# ZYNQ400-DDR.net
KiCad netlist of a schematic drawn in Altium Designer
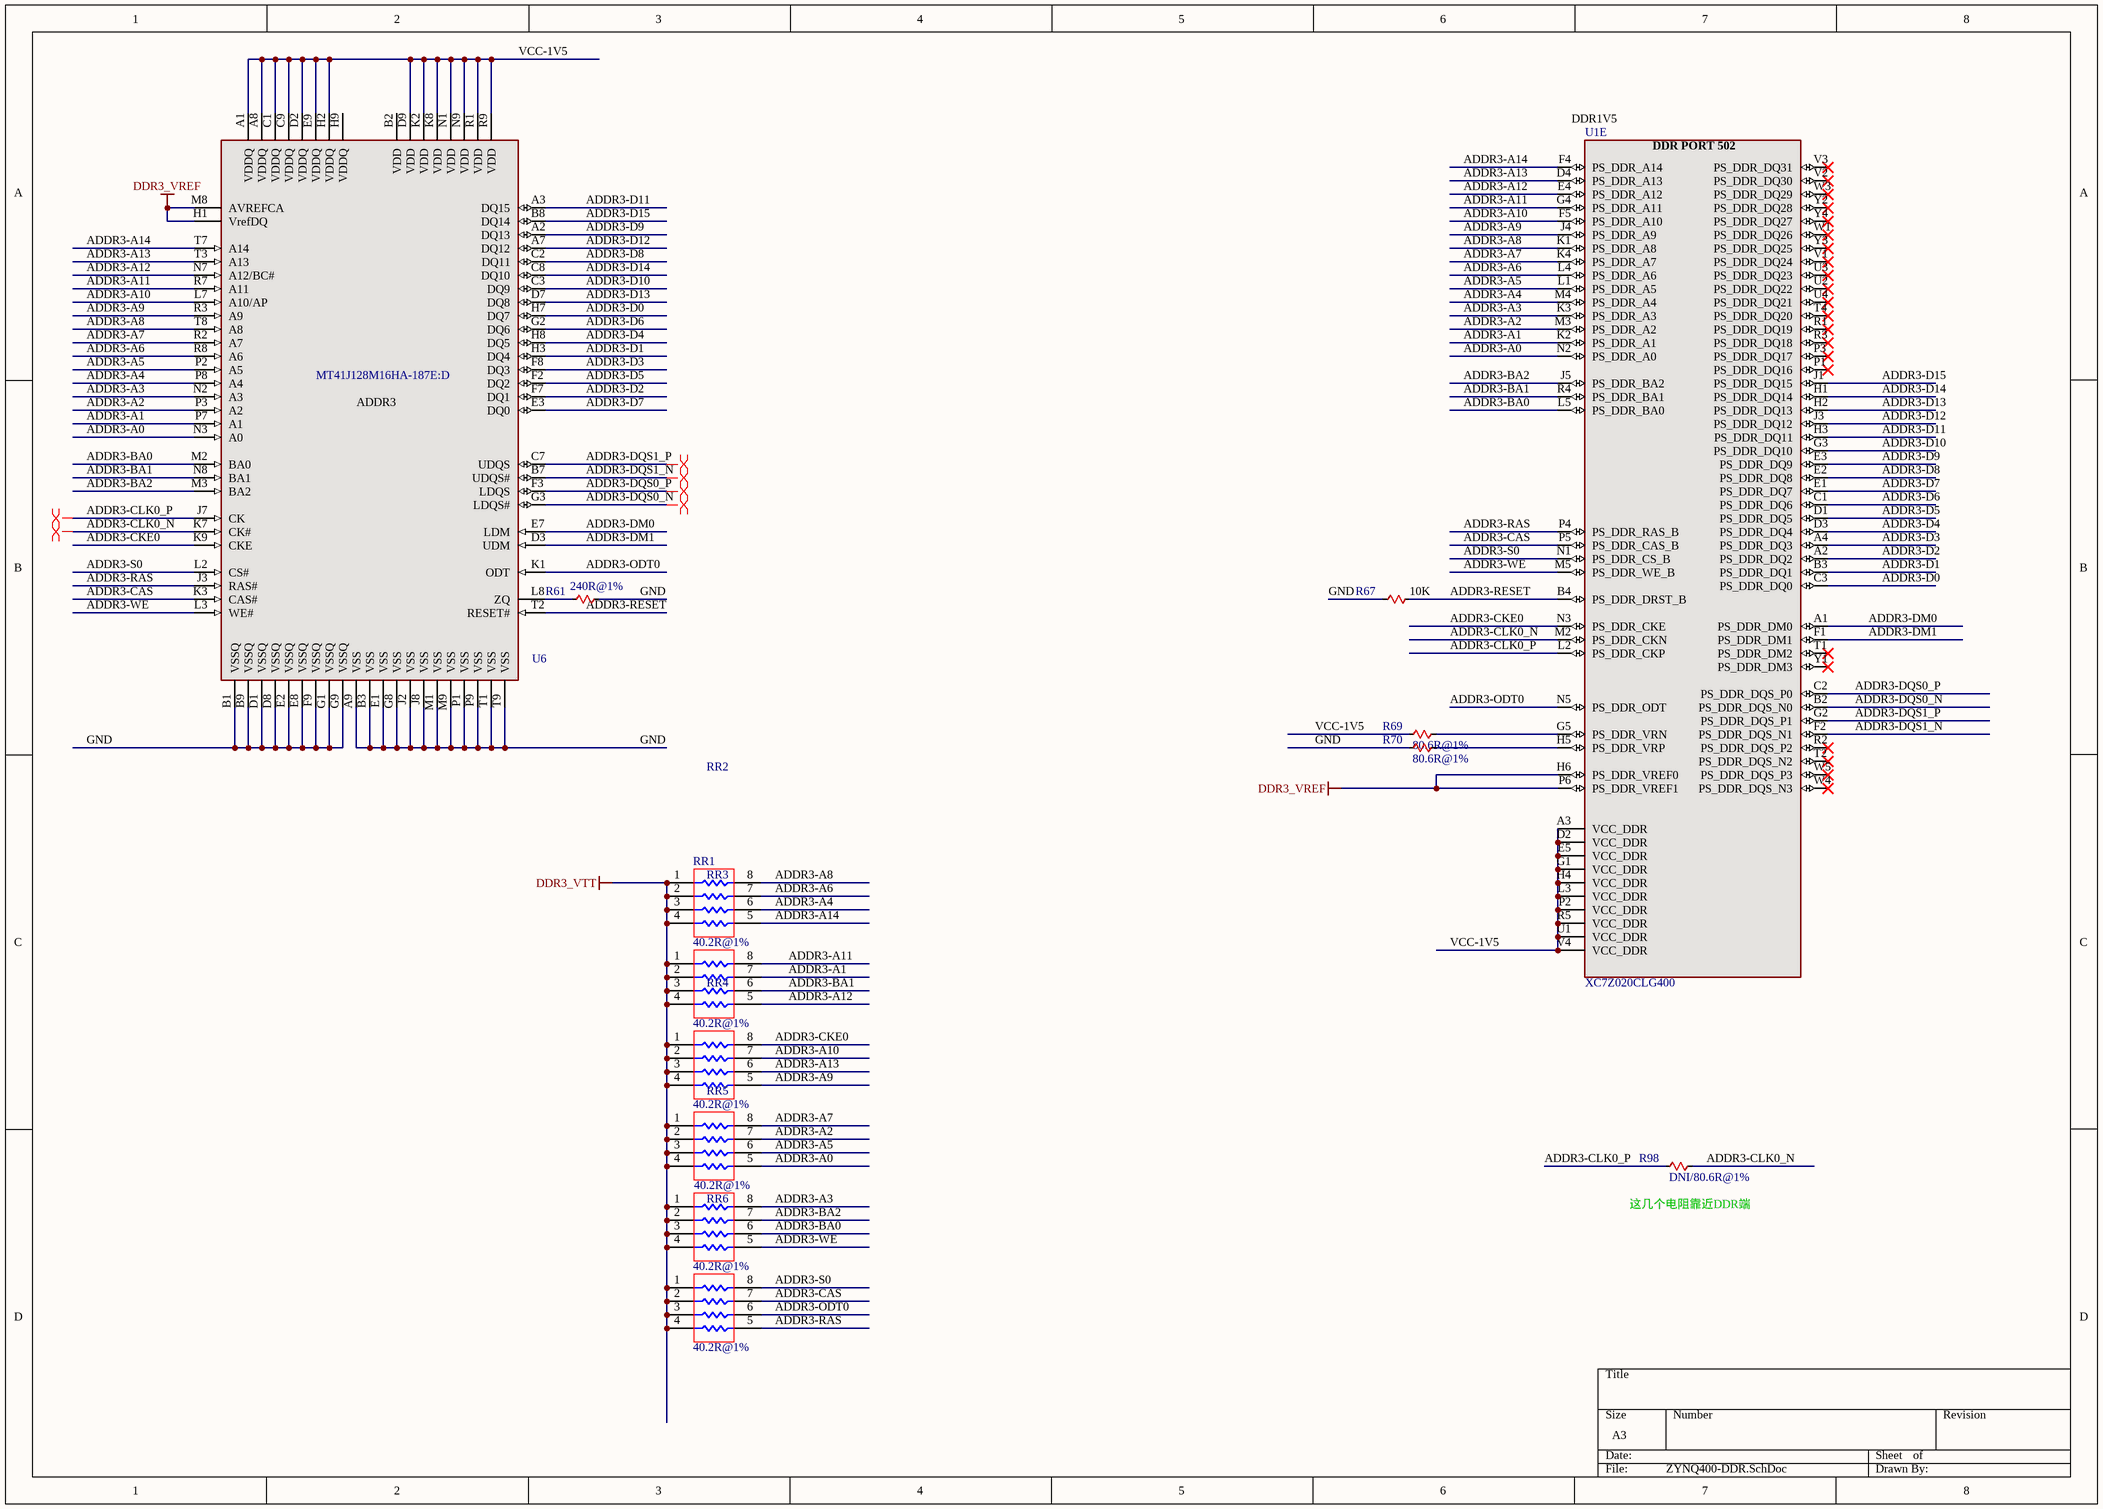
[diagram p0: ZYNQ400-DDR.SchDoc]

(export (version "E")
  (design (tool "Eeschema 10.0.6"))
  (components
    (comp (ref "R61")
      (value "240R@1%")
      (footprint "0402")
      (description "Generic Resistor")
      (libsource (lib "Digilent") (part "RESISTOR"))
    )
    (comp (ref "R67")
      (value "10K")
      (footprint "0402")
      (description "Generic Resistor")
      (libsource (lib "Digilent") (part "RESISTOR"))
    )
    (comp (ref "R69")
      (value "80.6R@1%")
      (footprint "0402")
      (description "Generic Resistor")
      (libsource (lib "Digilent") (part "RESISTOR"))
    )
    (comp (ref "R70")
      (value "80.6R@1%")
      (footprint "0402")
      (description "Generic Resistor")
      (libsource (lib "Digilent") (part "RESISTOR"))
    )
    (comp (ref "R98")
      (value "DNI/80.6R@1%")
      (footprint "0402")
      (description "Generic Resistor")
      (libsource (lib "Digilent") (part "RESISTOR"))
    )
    (comp (ref "RR1")
      (value "40.2R@1%")
      (footprint "R0402*4")
      (description "Isolated Resistor Network")
      (fields (field (name "PUBLISHER") "Altium Limited"))
      (libsource (lib "ipc400") (part "Res -4"))
    )
    (comp (ref "RR2")
      (value "40.2R@1%")
      (footprint "R0402*4")
      (description "Isolated Resistor Network")
      (fields (field (name "PUBLISHER") "Altium Limited"))
      (libsource (lib "ipc400") (part "Res -4"))
    )
    (comp (ref "RR3")
      (value "40.2R@1%")
      (footprint "R0402*4")
      (description "Isolated Resistor Network")
      (fields (field (name "PUBLISHER") "Altium Limited"))
      (libsource (lib "ipc400") (part "Res -4"))
    )
    (comp (ref "RR4")
      (value "40.2R@1%")
      (footprint "R0402*4")
      (description "Isolated Resistor Network")
      (fields (field (name "PUBLISHER") "Altium Limited"))
      (libsource (lib "ipc400") (part "Res -4"))
    )
    (comp (ref "RR5")
      (value "40.2R@1%")
      (footprint "R0402*4")
      (description "Isolated Resistor Network")
      (fields (field (name "PUBLISHER") "Altium Limited"))
      (libsource (lib "ipc400") (part "Res -4"))
    )
    (comp (ref "RR6")
      (value "40.2R@1%")
      (footprint "R0402*4")
      (description "Isolated Resistor Network")
      (fields (field (name "PUBLISHER") "Altium Limited"))
      (libsource (lib "ipc400") (part "Res -4"))
    )
    (comp (ref "U1")
      (value "XC7Z020CLG400")
      (footprint "CLG400")
      (description "Zynq 7000 FPGA 20 Die, in a CSG 484 Package")
      (fields (field (name "MANUFACTURER") "Xilinx"))
      (libsource (lib "gjws") (part "XC7Z020-CLG400"))
    )
    (comp (ref "U6")
      (value "MT41J128M16HA-187E:D")
      (footprint "FBGA96")
      (description "DDR3 SDRAM 2Gb x4, x8, x16")
      (fields (field (name "MANUFACTURER") "Micron"))
      (libsource (lib "Digilent") (part "MT41JxxxMxx"))
    )
  )
  (nets
    (net (code "1") (name "/ADDR3-A0") (class "Default")
      (node (ref "RR4") (pin "5") (pinfunction "5_5") (pintype "passive"))
      (node (ref "U1") (pin "N2") (pinfunction "PS_DDR_A0_N2") (pintype "bidirectional"))
      (node (ref "U6") (pin "N3") (pinfunction "A0_N3") (pintype "input"))
    )
    (net (code "2") (name "/ADDR3-A1") (class "Default")
      (node (ref "RR2") (pin "7") (pinfunction "7_7") (pintype "passive"))
      (node (ref "U1") (pin "K2") (pinfunction "PS_DDR_A1_K2") (pintype "bidirectional"))
      (node (ref "U6") (pin "P7") (pinfunction "A1_P7") (pintype "input"))
    )
    (net (code "3") (name "/ADDR3-A2") (class "Default")
      (node (ref "RR4") (pin "7") (pinfunction "7_7") (pintype "passive"))
      (node (ref "U1") (pin "M3") (pinfunction "PS_DDR_A2_M3") (pintype "bidirectional"))
      (node (ref "U6") (pin "P3") (pinfunction "A2_P3") (pintype "input"))
    )
    (net (code "4") (name "/ADDR3-A3") (class "Default")
      (node (ref "RR5") (pin "8") (pinfunction "8_8") (pintype "passive"))
      (node (ref "U1") (pin "K3") (pinfunction "PS_DDR_A3_K3") (pintype "bidirectional"))
      (node (ref "U6") (pin "N2") (pinfunction "A3_N2") (pintype "input"))
    )
    (net (code "5") (name "/ADDR3-A4") (class "Default")
      (node (ref "RR1") (pin "6") (pinfunction "6_6") (pintype "passive"))
      (node (ref "U1") (pin "M4") (pinfunction "PS_DDR_A4_M4") (pintype "bidirectional"))
      (node (ref "U6") (pin "P8") (pinfunction "A4_P8") (pintype "input"))
    )
    (net (code "6") (name "/ADDR3-A5") (class "Default")
      (node (ref "RR4") (pin "6") (pinfunction "6_6") (pintype "passive"))
      (node (ref "U1") (pin "L1") (pinfunction "PS_DDR_A5_L1") (pintype "bidirectional"))
      (node (ref "U6") (pin "P2") (pinfunction "A5_P2") (pintype "input"))
    )
    (net (code "7") (name "/ADDR3-A6") (class "Default")
      (node (ref "RR1") (pin "7") (pinfunction "7_7") (pintype "passive"))
      (node (ref "U1") (pin "L4") (pinfunction "PS_DDR_A6_L4") (pintype "bidirectional"))
      (node (ref "U6") (pin "R8") (pinfunction "A6_R8") (pintype "input"))
    )
    (net (code "8") (name "/ADDR3-A7") (class "Default")
      (node (ref "RR4") (pin "8") (pinfunction "8_8") (pintype "passive"))
      (node (ref "U1") (pin "K4") (pinfunction "PS_DDR_A7_K4") (pintype "bidirectional"))
      (node (ref "U6") (pin "R2") (pinfunction "A7_R2") (pintype "input"))
    )
    (net (code "9") (name "/ADDR3-A8") (class "Default")
      (node (ref "RR1") (pin "8") (pinfunction "8_8") (pintype "passive"))
      (node (ref "U1") (pin "K1") (pinfunction "PS_DDR_A8_K1") (pintype "bidirectional"))
      (node (ref "U6") (pin "T8") (pinfunction "A8_T8") (pintype "input"))
    )
    (net (code "10") (name "/ADDR3-A9") (class "Default")
      (node (ref "RR3") (pin "5") (pinfunction "5_5") (pintype "passive"))
      (node (ref "U1") (pin "J4") (pinfunction "PS_DDR_A9_J4") (pintype "bidirectional"))
      (node (ref "U6") (pin "R3") (pinfunction "A9_R3") (pintype "input"))
    )
    (net (code "11") (name "/ADDR3-A10") (class "Default")
      (node (ref "RR3") (pin "7") (pinfunction "7_7") (pintype "passive"))
      (node (ref "U1") (pin "F5") (pinfunction "PS_DDR_A10_F5") (pintype "bidirectional"))
      (node (ref "U6") (pin "L7") (pinfunction "A10/AP_L7") (pintype "input"))
    )
    (net (code "12") (name "/ADDR3-A11") (class "Default")
      (node (ref "RR2") (pin "8") (pinfunction "8_8") (pintype "passive"))
      (node (ref "U1") (pin "G4") (pinfunction "PS_DDR_A11_G4") (pintype "bidirectional"))
      (node (ref "U6") (pin "R7") (pinfunction "A11_R7") (pintype "input"))
    )
    (net (code "13") (name "/ADDR3-A12") (class "Default")
      (node (ref "RR2") (pin "5") (pinfunction "5_5") (pintype "passive"))
      (node (ref "U1") (pin "E4") (pinfunction "PS_DDR_A12_E4") (pintype "bidirectional"))
      (node (ref "U6") (pin "N7") (pinfunction "A12/BC#_N7") (pintype "input"))
    )
    (net (code "14") (name "/ADDR3-A13") (class "Default")
      (node (ref "RR3") (pin "6") (pinfunction "6_6") (pintype "passive"))
      (node (ref "U1") (pin "D4") (pinfunction "PS_DDR_A13_D4") (pintype "bidirectional"))
      (node (ref "U6") (pin "T3") (pinfunction "A13_T3") (pintype "input"))
    )
    (net (code "15") (name "/ADDR3-A14") (class "Default")
      (node (ref "RR1") (pin "5") (pinfunction "5_5") (pintype "passive"))
      (node (ref "U1") (pin "F4") (pinfunction "PS_DDR_A14_F4") (pintype "bidirectional"))
      (node (ref "U6") (pin "T7") (pinfunction "A14_T7") (pintype "input"))
    )
    (net (code "16") (name "/ADDR3-BA0") (class "Default")
      (node (ref "RR5") (pin "6") (pinfunction "6_6") (pintype "passive"))
      (node (ref "U1") (pin "L5") (pinfunction "PS_DDR_BA0_L5") (pintype "bidirectional"))
      (node (ref "U6") (pin "M2") (pinfunction "BA0_M2") (pintype "input"))
    )
    (net (code "17") (name "/ADDR3-BA1") (class "Default")
      (node (ref "RR2") (pin "6") (pinfunction "6_6") (pintype "passive"))
      (node (ref "U1") (pin "R4") (pinfunction "PS_DDR_BA1_R4") (pintype "bidirectional"))
      (node (ref "U6") (pin "N8") (pinfunction "BA1_N8") (pintype "input"))
    )
    (net (code "18") (name "/ADDR3-BA2") (class "Default")
      (node (ref "RR5") (pin "7") (pinfunction "7_7") (pintype "passive"))
      (node (ref "U1") (pin "J5") (pinfunction "PS_DDR_BA2_J5") (pintype "bidirectional"))
      (node (ref "U6") (pin "M3") (pinfunction "BA2_M3") (pintype "input"))
    )
    (net (code "19") (name "/ADDR3-CAS") (class "Default")
      (node (ref "RR6") (pin "7") (pinfunction "7_7") (pintype "passive"))
      (node (ref "U1") (pin "P5") (pinfunction "PS_DDR_CAS_B_P5") (pintype "bidirectional"))
      (node (ref "U6") (pin "K3") (pinfunction "CAS#_K3") (pintype "input"))
    )
    (net (code "20") (name "/ADDR3-CKE0") (class "Default")
      (node (ref "RR3") (pin "8") (pinfunction "8_8") (pintype "passive"))
      (node (ref "U1") (pin "N3") (pinfunction "PS_DDR_CKE_N3") (pintype "bidirectional"))
      (node (ref "U6") (pin "K9") (pinfunction "CKE_K9") (pintype "input"))
    )
    (net (code "21") (name "/ADDR3-CLK0_N") (class "Default")
      (node (ref "R98") (pin "2") (pinfunction "2_2") (pintype "passive"))
      (node (ref "U1") (pin "M2") (pinfunction "PS_DDR_CKN_M2") (pintype "bidirectional"))
      (node (ref "U6") (pin "K7") (pinfunction "CK#_K7") (pintype "input"))
    )
    (net (code "22") (name "/ADDR3-CLK0_P") (class "Default")
      (node (ref "R98") (pin "1") (pinfunction "1_1") (pintype "passive"))
      (node (ref "U1") (pin "L2") (pinfunction "PS_DDR_CKP_L2") (pintype "bidirectional"))
      (node (ref "U6") (pin "J7") (pinfunction "CK_J7") (pintype "input"))
    )
    (net (code "23") (name "/ADDR3-D0") (class "Default")
      (node (ref "U1") (pin "C3") (pinfunction "PS_DDR_DQ0_C3") (pintype "bidirectional"))
      (node (ref "U6") (pin "H7") (pinfunction "DQ7_H7") (pintype "bidirectional"))
    )
    (net (code "24") (name "/ADDR3-D1") (class "Default")
      (node (ref "U1") (pin "B3") (pinfunction "PS_DDR_DQ1_B3") (pintype "bidirectional"))
      (node (ref "U6") (pin "H3") (pinfunction "DQ4_H3") (pintype "bidirectional"))
    )
    (net (code "25") (name "/ADDR3-D2") (class "Default")
      (node (ref "U1") (pin "A2") (pinfunction "PS_DDR_DQ2_A2") (pintype "bidirectional"))
      (node (ref "U6") (pin "F7") (pinfunction "DQ1_F7") (pintype "bidirectional"))
    )
    (net (code "26") (name "/ADDR3-D3") (class "Default")
      (node (ref "U1") (pin "A4") (pinfunction "PS_DDR_DQ3_A4") (pintype "bidirectional"))
      (node (ref "U6") (pin "F8") (pinfunction "DQ3_F8") (pintype "bidirectional"))
    )
    (net (code "27") (name "/ADDR3-D4") (class "Default")
      (node (ref "U1") (pin "D3") (pinfunction "PS_DDR_DQ4_D3") (pintype "bidirectional"))
      (node (ref "U6") (pin "H8") (pinfunction "DQ5_H8") (pintype "bidirectional"))
    )
    (net (code "28") (name "/ADDR3-D5") (class "Default")
      (node (ref "U1") (pin "D1") (pinfunction "PS_DDR_DQ5_D1") (pintype "bidirectional"))
      (node (ref "U6") (pin "F2") (pinfunction "DQ2_F2") (pintype "bidirectional"))
    )
    (net (code "29") (name "/ADDR3-D6") (class "Default")
      (node (ref "U1") (pin "C1") (pinfunction "PS_DDR_DQ6_C1") (pintype "bidirectional"))
      (node (ref "U6") (pin "G2") (pinfunction "DQ6_G2") (pintype "bidirectional"))
    )
    (net (code "30") (name "/ADDR3-D7") (class "Default")
      (node (ref "U1") (pin "E1") (pinfunction "PS_DDR_DQ7_E1") (pintype "bidirectional"))
      (node (ref "U6") (pin "E3") (pinfunction "DQ0_E3") (pintype "bidirectional"))
    )
    (net (code "31") (name "/ADDR3-D8") (class "Default")
      (node (ref "U1") (pin "E2") (pinfunction "PS_DDR_DQ8_E2") (pintype "bidirectional"))
      (node (ref "U6") (pin "C2") (pinfunction "DQ11_C2") (pintype "bidirectional"))
    )
    (net (code "32") (name "/ADDR3-D9") (class "Default")
      (node (ref "U1") (pin "E3") (pinfunction "PS_DDR_DQ9_E3") (pintype "bidirectional"))
      (node (ref "U6") (pin "A2") (pinfunction "DQ13_A2") (pintype "bidirectional"))
    )
    (net (code "33") (name "/ADDR3-D10") (class "Default")
      (node (ref "U1") (pin "G3") (pinfunction "PS_DDR_DQ10_G3") (pintype "bidirectional"))
      (node (ref "U6") (pin "C3") (pinfunction "DQ9_C3") (pintype "bidirectional"))
    )
    (net (code "34") (name "/ADDR3-D11") (class "Default")
      (node (ref "U1") (pin "H3") (pinfunction "PS_DDR_DQ11_H3") (pintype "bidirectional"))
      (node (ref "U6") (pin "A3") (pinfunction "DQ15_A3") (pintype "bidirectional"))
    )
    (net (code "35") (name "/ADDR3-D12") (class "Default")
      (node (ref "U1") (pin "J3") (pinfunction "PS_DDR_DQ12_J3") (pintype "bidirectional"))
      (node (ref "U6") (pin "A7") (pinfunction "DQ12_A7") (pintype "bidirectional"))
    )
    (net (code "36") (name "/ADDR3-D13") (class "Default")
      (node (ref "U1") (pin "H2") (pinfunction "PS_DDR_DQ13_H2") (pintype "bidirectional"))
      (node (ref "U6") (pin "D7") (pinfunction "DQ8_D7") (pintype "bidirectional"))
    )
    (net (code "37") (name "/ADDR3-D14") (class "Default")
      (node (ref "U1") (pin "H1") (pinfunction "PS_DDR_DQ14_H1") (pintype "bidirectional"))
      (node (ref "U6") (pin "C8") (pinfunction "DQ10_C8") (pintype "bidirectional"))
    )
    (net (code "38") (name "/ADDR3-D15") (class "Default")
      (node (ref "U1") (pin "J1") (pinfunction "PS_DDR_DQ15_J1") (pintype "bidirectional"))
      (node (ref "U6") (pin "B8") (pinfunction "DQ14_B8") (pintype "bidirectional"))
    )
    (net (code "39") (name "/ADDR3-DM0") (class "Default")
      (node (ref "U1") (pin "A1") (pinfunction "PS_DDR_DM0_A1") (pintype "bidirectional"))
      (node (ref "U6") (pin "E7") (pinfunction "LDM_E7") (pintype "input"))
    )
    (net (code "40") (name "/ADDR3-DM1") (class "Default")
      (node (ref "U1") (pin "F1") (pinfunction "PS_DDR_DM1_F1") (pintype "bidirectional"))
      (node (ref "U6") (pin "D3") (pinfunction "UDM_D3") (pintype "input"))
    )
    (net (code "41") (name "/ADDR3-DQS0_N") (class "Default")
      (node (ref "U1") (pin "B2") (pinfunction "PS_DDR_DQS_N0_B2") (pintype "bidirectional"))
      (node (ref "U6") (pin "G3") (pinfunction "LDQS#_G3") (pintype "bidirectional"))
    )
    (net (code "42") (name "/ADDR3-DQS0_P") (class "Default")
      (node (ref "U1") (pin "C2") (pinfunction "PS_DDR_DQS_P0_C2") (pintype "bidirectional"))
      (node (ref "U6") (pin "F3") (pinfunction "LDQS_F3") (pintype "bidirectional"))
    )
    (net (code "43") (name "/ADDR3-DQS1_N") (class "Default")
      (node (ref "U1") (pin "F2") (pinfunction "PS_DDR_DQS_N1_F2") (pintype "bidirectional"))
      (node (ref "U6") (pin "B7") (pinfunction "UDQS#_B7") (pintype "bidirectional"))
    )
    (net (code "44") (name "/ADDR3-DQS1_P") (class "Default")
      (node (ref "U1") (pin "G2") (pinfunction "PS_DDR_DQS_P1_G2") (pintype "bidirectional"))
      (node (ref "U6") (pin "C7") (pinfunction "UDQS_C7") (pintype "bidirectional"))
    )
    (net (code "45") (name "/ADDR3-ODT0") (class "Default")
      (node (ref "RR6") (pin "6") (pinfunction "6_6") (pintype "passive"))
      (node (ref "U1") (pin "N5") (pinfunction "PS_DDR_ODT_N5") (pintype "bidirectional"))
      (node (ref "U6") (pin "K1") (pinfunction "ODT_K1") (pintype "input"))
    )
    (net (code "46") (name "/ADDR3-RAS") (class "Default")
      (node (ref "RR6") (pin "5") (pinfunction "5_5") (pintype "passive"))
      (node (ref "U1") (pin "P4") (pinfunction "PS_DDR_RAS_B_P4") (pintype "bidirectional"))
      (node (ref "U6") (pin "J3") (pinfunction "RAS#_J3") (pintype "input"))
    )
    (net (code "47") (name "/ADDR3-RESET") (class "Default")
      (node (ref "R67") (pin "1") (pinfunction "1_1") (pintype "passive"))
      (node (ref "U1") (pin "B4") (pinfunction "PS_DDR_DRST_B_B4") (pintype "bidirectional"))
      (node (ref "U6") (pin "T2") (pinfunction "RESET#_T2") (pintype "input"))
    )
    (net (code "48") (name "/ADDR3-S0") (class "Default")
      (node (ref "RR6") (pin "8") (pinfunction "8_8") (pintype "passive"))
      (node (ref "U1") (pin "N1") (pinfunction "PS_DDR_CS_B_N1") (pintype "bidirectional"))
      (node (ref "U6") (pin "L2") (pinfunction "CS#_L2") (pintype "input"))
    )
    (net (code "49") (name "/ADDR3-WE") (class "Default")
      (node (ref "RR5") (pin "5") (pinfunction "5_5") (pintype "passive"))
      (node (ref "U1") (pin "M5") (pinfunction "PS_DDR_WE_B_M5") (pintype "bidirectional"))
      (node (ref "U6") (pin "L3") (pinfunction "WE#_L3") (pintype "input"))
    )
    (net (code "50") (name "/GND") (class "Default")
      (node (ref "R61") (pin "2") (pinfunction "2_2") (pintype "passive"))
      (node (ref "R67") (pin "2") (pinfunction "2_2") (pintype "passive"))
      (node (ref "R70") (pin "1") (pinfunction "1_1") (pintype "passive"))
      (node (ref "U6") (pin "A9") (pinfunction "VSS_A9") (pintype "power_in"))
      (node (ref "U6") (pin "B1") (pinfunction "VSSQ_B1") (pintype "power_in"))
      (node (ref "U6") (pin "B3") (pinfunction "VSS_B3") (pintype "power_in"))
      (node (ref "U6") (pin "B9") (pinfunction "VSSQ_B9") (pintype "power_in"))
      (node (ref "U6") (pin "D1") (pinfunction "VSSQ_D1") (pintype "power_in"))
      (node (ref "U6") (pin "D8") (pinfunction "VSSQ_D8") (pintype "power_in"))
      (node (ref "U6") (pin "E1") (pinfunction "VSS_E1") (pintype "power_in"))
      (node (ref "U6") (pin "E2") (pinfunction "VSSQ_E2") (pintype "power_in"))
      (node (ref "U6") (pin "E8") (pinfunction "VSSQ_E8") (pintype "power_in"))
      (node (ref "U6") (pin "F9") (pinfunction "VSSQ_F9") (pintype "power_in"))
      (node (ref "U6") (pin "G1") (pinfunction "VSSQ_G1") (pintype "power_in"))
      (node (ref "U6") (pin "G8") (pinfunction "VSS_G8") (pintype "power_in"))
      (node (ref "U6") (pin "G9") (pinfunction "VSSQ_G9") (pintype "power_in"))
      (node (ref "U6") (pin "J2") (pinfunction "VSS_J2") (pintype "power_in"))
      (node (ref "U6") (pin "J8") (pinfunction "VSS_J8") (pintype "power_in"))
      (node (ref "U6") (pin "M1") (pinfunction "VSS_M1") (pintype "power_in"))
      (node (ref "U6") (pin "M9") (pinfunction "VSS_M9") (pintype "power_in"))
      (node (ref "U6") (pin "P1") (pinfunction "VSS_P1") (pintype "power_in"))
      (node (ref "U6") (pin "P9") (pinfunction "VSS_P9") (pintype "power_in"))
      (node (ref "U6") (pin "T1") (pinfunction "VSS_T1") (pintype "power_in"))
      (node (ref "U6") (pin "T9") (pinfunction "VSS_T9") (pintype "power_in"))
    )
    (net (code "51") (name "/VCC-1V5") (class "Default")
      (node (ref "R69") (pin "1") (pinfunction "1_1") (pintype "passive"))
      (node (ref "U1") (pin "A3") (pinfunction "VCC_DDR_A3") (pintype "power_in"))
      (node (ref "U1") (pin "D2") (pinfunction "VCC_DDR_D2") (pintype "power_in"))
      (node (ref "U1") (pin "E5") (pinfunction "VCC_DDR_E5") (pintype "power_in"))
      (node (ref "U1") (pin "G1") (pinfunction "VCC_DDR_G1") (pintype "power_in"))
      (node (ref "U1") (pin "H4") (pinfunction "VCC_DDR_H4") (pintype "power_in"))
      (node (ref "U1") (pin "L3") (pinfunction "VCC_DDR_L3") (pintype "power_in"))
      (node (ref "U1") (pin "P2") (pinfunction "VCC_DDR_P2") (pintype "power_in"))
      (node (ref "U1") (pin "R5") (pinfunction "VCC_DDR_R5") (pintype "power_in"))
      (node (ref "U1") (pin "U1") (pinfunction "VCC_DDR_U1") (pintype "power_in"))
      (node (ref "U1") (pin "V4") (pinfunction "VCC_DDR_V4") (pintype "power_in"))
      (node (ref "U6") (pin "A1") (pinfunction "VDDQ_A1") (pintype "power_in"))
      (node (ref "U6") (pin "A8") (pinfunction "VDDQ_A8") (pintype "power_in"))
      (node (ref "U6") (pin "C1") (pinfunction "VDDQ_C1") (pintype "power_in"))
      (node (ref "U6") (pin "C9") (pinfunction "VDDQ_C9") (pintype "power_in"))
      (node (ref "U6") (pin "D2") (pinfunction "VDDQ_D2") (pintype "power_in"))
      (node (ref "U6") (pin "D9") (pinfunction "VDD_D9") (pintype "power_in"))
      (node (ref "U6") (pin "E9") (pinfunction "VDDQ_E9") (pintype "power_in"))
      (node (ref "U6") (pin "H2") (pinfunction "VDDQ_H2") (pintype "power_in"))
      (node (ref "U6") (pin "K2") (pinfunction "VDD_K2") (pintype "power_in"))
      (node (ref "U6") (pin "K8") (pinfunction "VDD_K8") (pintype "power_in"))
      (node (ref "U6") (pin "N1") (pinfunction "VDD_N1") (pintype "power_in"))
      (node (ref "U6") (pin "N9") (pinfunction "VDD_N9") (pintype "power_in"))
      (node (ref "U6") (pin "R1") (pinfunction "VDD_R1") (pintype "power_in"))
      (node (ref "U6") (pin "R9") (pinfunction "VDD_R9") (pintype "power_in"))
    )
    (net (code "52") (name "DDR3_VREF") (class "Default")
      (node (ref "U1") (pin "H6") (pinfunction "PS_DDR_VREF0_H6") (pintype "bidirectional"))
      (node (ref "U1") (pin "P6") (pinfunction "PS_DDR_VREF1_P6") (pintype "bidirectional"))
      (node (ref "U6") (pin "H1") (pinfunction "VrefDQ_H1") (pintype "power_in"))
      (node (ref "U6") (pin "M8") (pinfunction "AVREFCA_M8") (pintype "power_in"))
    )
    (net (code "53") (name "DDR3_VTT") (class "Default")
      (node (ref "RR1") (pin "1") (pinfunction "1_1") (pintype "passive"))
      (node (ref "RR1") (pin "2") (pinfunction "2_2") (pintype "passive"))
      (node (ref "RR1") (pin "3") (pinfunction "3_3") (pintype "passive"))
      (node (ref "RR1") (pin "4") (pinfunction "4_4") (pintype "passive"))
      (node (ref "RR2") (pin "1") (pinfunction "1_1") (pintype "passive"))
      (node (ref "RR2") (pin "2") (pinfunction "2_2") (pintype "passive"))
      (node (ref "RR2") (pin "3") (pinfunction "3_3") (pintype "passive"))
      (node (ref "RR2") (pin "4") (pinfunction "4_4") (pintype "passive"))
      (node (ref "RR3") (pin "1") (pinfunction "1_1") (pintype "passive"))
      (node (ref "RR3") (pin "2") (pinfunction "2_2") (pintype "passive"))
      (node (ref "RR3") (pin "3") (pinfunction "3_3") (pintype "passive"))
      (node (ref "RR3") (pin "4") (pinfunction "4_4") (pintype "passive"))
      (node (ref "RR4") (pin "1") (pinfunction "1_1") (pintype "passive"))
      (node (ref "RR4") (pin "2") (pinfunction "2_2") (pintype "passive"))
      (node (ref "RR4") (pin "3") (pinfunction "3_3") (pintype "passive"))
      (node (ref "RR4") (pin "4") (pinfunction "4_4") (pintype "passive"))
      (node (ref "RR5") (pin "1") (pinfunction "1_1") (pintype "passive"))
      (node (ref "RR5") (pin "2") (pinfunction "2_2") (pintype "passive"))
      (node (ref "RR5") (pin "3") (pinfunction "3_3") (pintype "passive"))
      (node (ref "RR5") (pin "4") (pinfunction "4_4") (pintype "passive"))
      (node (ref "RR6") (pin "1") (pinfunction "1_1") (pintype "passive"))
      (node (ref "RR6") (pin "2") (pinfunction "2_2") (pintype "passive"))
      (node (ref "RR6") (pin "3") (pinfunction "3_3") (pintype "passive"))
      (node (ref "RR6") (pin "4") (pinfunction "4_4") (pintype "passive"))
    )
    (net (code "54") (name "Net-(U1E-PS_DDR_VRN)") (class "Default")
      (node (ref "R69") (pin "2") (pinfunction "2_2") (pintype "passive"))
      (node (ref "U1") (pin "G5") (pinfunction "PS_DDR_VRN_G5") (pintype "bidirectional"))
    )
    (net (code "55") (name "Net-(U1E-PS_DDR_VRP)") (class "Default")
      (node (ref "R70") (pin "2") (pinfunction "2_2") (pintype "passive"))
      (node (ref "U1") (pin "H5") (pinfunction "PS_DDR_VRP_H5") (pintype "bidirectional"))
    )
    (net (code "56") (name "Net-(U6-ZQ)") (class "Default")
      (node (ref "R61") (pin "1") (pinfunction "1_1") (pintype "passive"))
      (node (ref "U6") (pin "L8") (pinfunction "ZQ_L8") (pintype "passive"))
    )
    (net (code "57") (name "unconnected-(U1E-PS_DDR_DM2-PadT1)") (class "Default")
      (node (ref "U1") (pin "T1") (pinfunction "PS_DDR_DM2_T1") (pintype "bidirectional+no_connect"))
    )
    (net (code "58") (name "unconnected-(U1E-PS_DDR_DM3-PadY1)") (class "Default")
      (node (ref "U1") (pin "Y1") (pinfunction "PS_DDR_DM3_Y1") (pintype "bidirectional+no_connect"))
    )
    (net (code "59") (name "unconnected-(U1E-PS_DDR_DQ16-PadP1)") (class "Default")
      (node (ref "U1") (pin "P1") (pinfunction "PS_DDR_DQ16_P1") (pintype "bidirectional+no_connect"))
    )
    (net (code "60") (name "unconnected-(U1E-PS_DDR_DQ17-PadP3)") (class "Default")
      (node (ref "U1") (pin "P3") (pinfunction "PS_DDR_DQ17_P3") (pintype "bidirectional+no_connect"))
    )
    (net (code "61") (name "unconnected-(U1E-PS_DDR_DQ18-PadR3)") (class "Default")
      (node (ref "U1") (pin "R3") (pinfunction "PS_DDR_DQ18_R3") (pintype "bidirectional+no_connect"))
    )
    (net (code "62") (name "unconnected-(U1E-PS_DDR_DQ19-PadR1)") (class "Default")
      (node (ref "U1") (pin "R1") (pinfunction "PS_DDR_DQ19_R1") (pintype "bidirectional+no_connect"))
    )
    (net (code "63") (name "unconnected-(U1E-PS_DDR_DQ20-PadT4)") (class "Default")
      (node (ref "U1") (pin "T4") (pinfunction "PS_DDR_DQ20_T4") (pintype "bidirectional+no_connect"))
    )
    (net (code "64") (name "unconnected-(U1E-PS_DDR_DQ21-PadU4)") (class "Default")
      (node (ref "U1") (pin "U4") (pinfunction "PS_DDR_DQ21_U4") (pintype "bidirectional+no_connect"))
    )
    (net (code "65") (name "unconnected-(U1E-PS_DDR_DQ22-PadU2)") (class "Default")
      (node (ref "U1") (pin "U2") (pinfunction "PS_DDR_DQ22_U2") (pintype "bidirectional+no_connect"))
    )
    (net (code "66") (name "unconnected-(U1E-PS_DDR_DQ23-PadU3)") (class "Default")
      (node (ref "U1") (pin "U3") (pinfunction "PS_DDR_DQ23_U3") (pintype "bidirectional+no_connect"))
    )
    (net (code "67") (name "unconnected-(U1E-PS_DDR_DQ24-PadV1)") (class "Default")
      (node (ref "U1") (pin "V1") (pinfunction "PS_DDR_DQ24_V1") (pintype "bidirectional+no_connect"))
    )
    (net (code "68") (name "unconnected-(U1E-PS_DDR_DQ25-PadY3)") (class "Default")
      (node (ref "U1") (pin "Y3") (pinfunction "PS_DDR_DQ25_Y3") (pintype "bidirectional+no_connect"))
    )
    (net (code "69") (name "unconnected-(U1E-PS_DDR_DQ26-PadW1)") (class "Default")
      (node (ref "U1") (pin "W1") (pinfunction "PS_DDR_DQ26_W1") (pintype "bidirectional+no_connect"))
    )
    (net (code "70") (name "unconnected-(U1E-PS_DDR_DQ27-PadY4)") (class "Default")
      (node (ref "U1") (pin "Y4") (pinfunction "PS_DDR_DQ27_Y4") (pintype "bidirectional+no_connect"))
    )
    (net (code "71") (name "unconnected-(U1E-PS_DDR_DQ28-PadY2)") (class "Default")
      (node (ref "U1") (pin "Y2") (pinfunction "PS_DDR_DQ28_Y2") (pintype "bidirectional+no_connect"))
    )
    (net (code "72") (name "unconnected-(U1E-PS_DDR_DQ29-PadW3)") (class "Default")
      (node (ref "U1") (pin "W3") (pinfunction "PS_DDR_DQ29_W3") (pintype "bidirectional+no_connect"))
    )
    (net (code "73") (name "unconnected-(U1E-PS_DDR_DQ30-PadV2)") (class "Default")
      (node (ref "U1") (pin "V2") (pinfunction "PS_DDR_DQ30_V2") (pintype "bidirectional+no_connect"))
    )
    (net (code "74") (name "unconnected-(U1E-PS_DDR_DQ31-PadV3)") (class "Default")
      (node (ref "U1") (pin "V3") (pinfunction "PS_DDR_DQ31_V3") (pintype "bidirectional+no_connect"))
    )
    (net (code "75") (name "unconnected-(U1E-PS_DDR_DQS_N2-PadT2)") (class "Default")
      (node (ref "U1") (pin "T2") (pinfunction "PS_DDR_DQS_N2_T2") (pintype "bidirectional+no_connect"))
    )
    (net (code "76") (name "unconnected-(U1E-PS_DDR_DQS_N3-PadW4)") (class "Default")
      (node (ref "U1") (pin "W4") (pinfunction "PS_DDR_DQS_N3_W4") (pintype "bidirectional+no_connect"))
    )
    (net (code "77") (name "unconnected-(U1E-PS_DDR_DQS_P2-PadR2)") (class "Default")
      (node (ref "U1") (pin "R2") (pinfunction "PS_DDR_DQS_P2_R2") (pintype "bidirectional+no_connect"))
    )
    (net (code "78") (name "unconnected-(U1E-PS_DDR_DQS_P3-PadW5)") (class "Default")
      (node (ref "U1") (pin "W5") (pinfunction "PS_DDR_DQS_P3_W5") (pintype "bidirectional+no_connect"))
    )
    (net (code "79") (name "unconnected-(U6-VDD-PadB2)") (class "Default")
      (node (ref "U6") (pin "B2") (pinfunction "VDD_B2") (pintype "power_in"))
    )
    (net (code "80") (name "unconnected-(U6-VDDQ-PadH9)") (class "Default")
      (node (ref "U6") (pin "H9") (pinfunction "VDDQ_H9") (pintype "power_in"))
    )
  )
)
